# 1602.net
KiCad netlist of a schematic drawn in Altium Designer
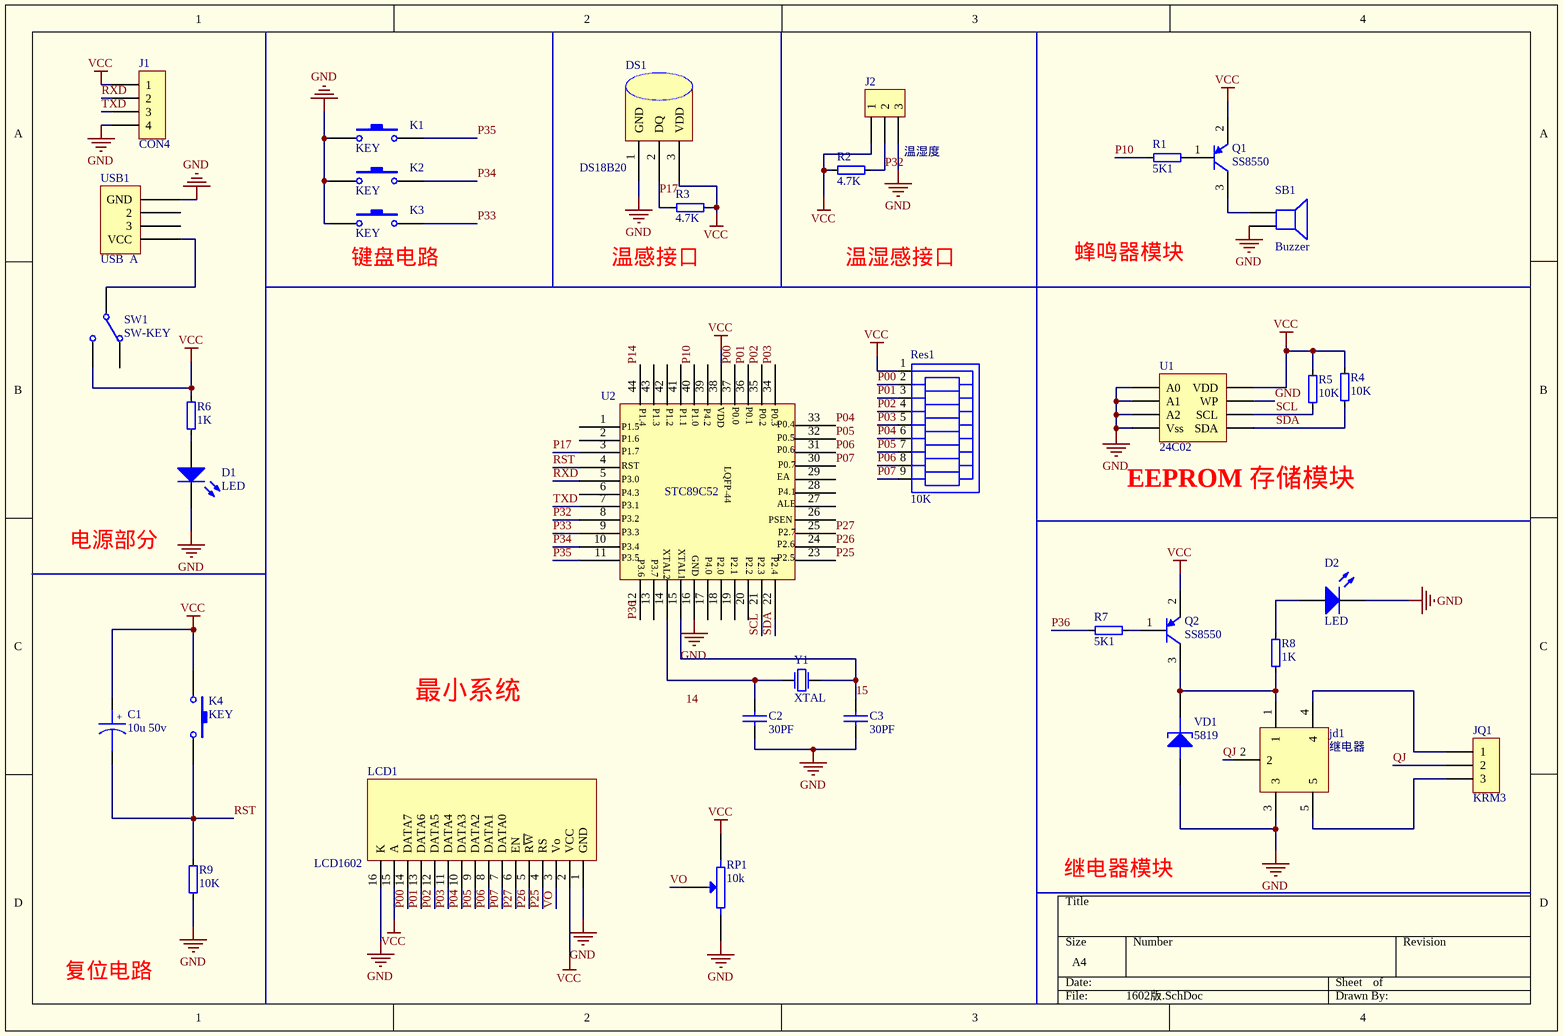
[diagram p0: 1602版.SchDoc]

(export (version "E")
  (design (tool "Eeschema 10.0.6"))
  (components
    (comp (ref "C1") (value "10u 50v") (footprint "10uf 50v") (libsource (lib "我的元件库2") (part "10u 50v")))
    (comp (ref "C2") (value "30PF") (footprint "C0805") (libsource (lib "阻容LED（集成）_Library") (part "CAP")))
    (comp (ref "C3") (value "30PF") (footprint "C0805") (libsource (lib "阻容LED（集成）_Library") (part "CAP")))
    (comp (ref "D1") (value "LED") (footprint "LED") (libsource (lib "我的元件库") (part "LED")))
    (comp (ref "D2") (value "LED") (footprint "LED") (libsource (lib "我的元件库") (part "LED")))
    (comp (ref "DS1") (value "DS18B20") (footprint "DS18B20") (libsource (lib "我的元件库") (part "DS18B20")))
    (comp (ref "J1") (value "CON4") (footprint "CON4") (libsource (lib "我的元件库2") (part "CON4")))
    (comp (ref "J2") (value "温湿度") (footprint "×3") (libsource (lib "我的元件库") (part "×3")))
    (comp (ref "jd1") (value "继电器") (footprint "继电器2") (libsource (lib "我的元件库2") (part "继电器2")))
    (comp (ref "JQ1") (value "KRM3") (footprint "KRM3") (libsource (lib "我的元件库2") (part "KRM3")))
    (comp (ref "K1") (value "KEY") (footprint "KEY") (libsource (lib "我的元件库") (part "KEY")))
    (comp (ref "K2") (value "KEY") (footprint "KEY") (libsource (lib "我的元件库") (part "KEY")))
    (comp (ref "K3") (value "KEY") (footprint "KEY") (libsource (lib "我的元件库") (part "KEY")))
    (comp (ref "K4") (value "KEY") (footprint "KEY") (libsource (lib "我的元件库") (part "KEY")))
    (comp (ref "LCD1") (value "LCD1602") (footprint "LCD1602") (libsource (lib "我的元件库2") (part "LCD1602")))
    (comp (ref "Q1")
      (value "SS8550")
      (footprint "SOT-23")
      (description "PNP贴片三极管")
      (fields (field (name "PUBLISHER") "Altium Limited"))
      (libsource (lib "Fszhang") (part "SS8550"))
    )
    (comp (ref "Q2")
      (value "SS8550")
      (footprint "SOT-23")
      (description "PNP贴片三极管")
      (fields (field (name "PUBLISHER") "Altium Limited"))
      (libsource (lib "Fszhang") (part "SS8550"))
    )
    (comp (ref "R1")
      (value "5K1")
      (footprint "R0805")
      (libsource (lib "阻容LED（集成）_Library") (part "RESistor"))
    )
    (comp (ref "R2")
      (value "4.7K")
      (footprint "R0805")
      (libsource (lib "阻容LED（集成）_Library") (part "RESistor"))
    )
    (comp (ref "R3")
      (value "4.7K")
      (footprint "R0805")
      (libsource (lib "阻容LED（集成）_Library") (part "RESistor"))
    )
    (comp (ref "R4")
      (value "10K")
      (footprint "R0805")
      (libsource (lib "阻容LED（集成）_Library") (part "RESistor"))
    )
    (comp (ref "R5")
      (value "10K")
      (footprint "R0805")
      (libsource (lib "阻容LED（集成）_Library") (part "RESistor"))
    )
    (comp (ref "R6") (value "1K") (footprint "R0805") (libsource (lib "阻容LED（集成）_Library") (part "RESistor")))
    (comp (ref "R7")
      (value "5K1")
      (footprint "R0805")
      (libsource (lib "阻容LED（集成）_Library") (part "RESistor"))
    )
    (comp (ref "R8") (value "1K") (footprint "R0805") (libsource (lib "阻容LED（集成）_Library") (part "RESistor")))
    (comp (ref "R9")
      (value "10K")
      (footprint "R0805")
      (libsource (lib "阻容LED（集成）_Library") (part "RESistor"))
    )
    (comp (ref "Res1") (value "10K") (footprint "Res-8") (libsource (lib "我的元件库2") (part "Res-8")))
    (comp (ref "RP1") (value "10k") (footprint "RE3296") (libsource (lib "我的元件库2") (part "RP1")))
    (comp (ref "SB1") (value "Buzzer") (footprint "BUZZER") (libsource (lib "我的元件库") (part "Buzzer")))
    (comp (ref "SW1") (value "SW-KEY") (footprint "SW-KEY") (libsource (lib "我的元件库") (part "SW-KEY")))
    (comp (ref "U1") (value "24C02") (footprint "24c02") (libsource (lib "我的元件库") (part "24C02")))
    (comp (ref "U2") (value "STC89C52") (footprint "TQFP-44") (libsource (lib "我的元件库") (part "STC89C----")))
    (comp (ref "USB1") (value "USB  A") (footprint "USB A") (libsource (lib "我的元件库2") (part "USB  A")))
    (comp (ref "VD1")
      (value "5819")
      (footprint "SS24二极管")
      (description "Tunnel FDiode")
      (libsource (lib "7971驱动板集成库Library1") (part "SS24二极管"))
    )
    (comp (ref "Y1") (value "XTAL") (footprint "XTAL") (libsource (lib "我的元件库2") (part "XTAL")))
  )
  (nets
    (net (code "2") (name "/15") (class "Default")
      (node (ref "C3") (pin "1") (pinfunction "1_1") (pintype "passive"))
      (node (ref "U2") (pin "15") (pinfunction "XTAL1_15") (pintype "passive"))
      (node (ref "Y1") (pin "2") (pinfunction "P2_2") (pintype "passive"))
    )
    (net (code "3") (name "/P00") (class "Default")
      (node (ref "LCD1") (pin "14") (pinfunction "DATA7_14") (pintype "passive"))
      (node (ref "Res1") (pin "2") (pintype "passive"))
      (node (ref "U2") (pin "37") (pinfunction "P0.0_37") (pintype "passive"))
    )
    (net (code "4") (name "/P01") (class "Default")
      (node (ref "LCD1") (pin "13") (pinfunction "DATA6_13") (pintype "passive"))
      (node (ref "Res1") (pin "3") (pintype "passive"))
      (node (ref "U2") (pin "36") (pinfunction "P0.1_36") (pintype "passive"))
    )
    (net (code "5") (name "/P02") (class "Default")
      (node (ref "LCD1") (pin "12") (pinfunction "DATA5_12") (pintype "passive"))
      (node (ref "Res1") (pin "4") (pintype "passive"))
      (node (ref "U2") (pin "35") (pinfunction "P0.2_35") (pintype "passive"))
    )
    (net (code "6") (name "/P03") (class "Default")
      (node (ref "LCD1") (pin "11") (pinfunction "DATA4_11") (pintype "passive"))
      (node (ref "Res1") (pin "5") (pintype "passive"))
      (node (ref "U2") (pin "34") (pinfunction "P0.3_34") (pintype "passive"))
    )
    (net (code "7") (name "/P04") (class "Default")
      (node (ref "LCD1") (pin "10") (pinfunction "DATA3_10") (pintype "passive"))
      (node (ref "Res1") (pin "6") (pintype "passive"))
      (node (ref "U2") (pin "33") (pinfunction "P0.4_33") (pintype "passive"))
    )
    (net (code "8") (name "/P05") (class "Default")
      (node (ref "LCD1") (pin "9") (pinfunction "DATA2_9") (pintype "passive"))
      (node (ref "Res1") (pin "7") (pintype "passive"))
      (node (ref "U2") (pin "32") (pinfunction "P0.5_32") (pintype "passive"))
    )
    (net (code "9") (name "/P06") (class "Default")
      (node (ref "LCD1") (pin "8") (pinfunction "DATA1_8") (pintype "passive"))
      (node (ref "Res1") (pin "8") (pintype "passive"))
      (node (ref "U2") (pin "31") (pinfunction "P0.6_31") (pintype "passive"))
    )
    (net (code "10") (name "/P07") (class "Default")
      (node (ref "LCD1") (pin "7") (pinfunction "DATA0_7") (pintype "passive"))
      (node (ref "Res1") (pin "9") (pintype "passive"))
      (node (ref "U2") (pin "30") (pinfunction "P0.7_30") (pintype "passive"))
    )
    (net (code "11") (name "/P10") (class "Default")
      (node (ref "R1") (pin "2") (pinfunction "2_2") (pintype "passive"))
      (node (ref "U2") (pin "40") (pinfunction "CLKOUT2/ADC0/P1.0_40") (pintype "passive"))
    )
    (net (code "12") (name "/P14") (class "Default")
      (node (ref "U2") (pin "44") (pinfunction "SS/CCP1/ADC4/P1.4_44") (pintype "passive"))
    )
    (net (code "13") (name "/P17") (class "Default")
      (node (ref "DS1") (pin "2") (pinfunction "DQ_2") (pintype "passive"))
      (node (ref "R3") (pin "2") (pinfunction "2_2") (pintype "passive"))
      (node (ref "U2") (pin "3") (pinfunction "MOSI/ADC67P1.7_3") (pintype "passive"))
    )
    (net (code "14") (name "/P25") (class "Default")
      (node (ref "LCD1") (pin "4") (pinfunction "RS_4") (pintype "passive"))
      (node (ref "U2") (pin "23") (pinfunction "P2.5/A13_23") (pintype "passive"))
    )
    (net (code "15") (name "/P26") (class "Default")
      (node (ref "LCD1") (pin "5") (pinfunction "R~{W}_5") (pintype "passive"))
      (node (ref "U2") (pin "24") (pinfunction "P2.6/A14_24") (pintype "passive"))
    )
    (net (code "16") (name "/P27") (class "Default")
      (node (ref "LCD1") (pin "6") (pinfunction "EN_6") (pintype "passive"))
      (node (ref "U2") (pin "25") (pinfunction "P2.7/A15_25") (pintype "passive"))
    )
    (net (code "17") (name "/P32") (class "Default")
      (node (ref "J2") (pin "2") (pinfunction "2_2") (pintype "passive"))
      (node (ref "R2") (pin "1") (pinfunction "1_1") (pintype "passive"))
      (node (ref "U2") (pin "8") (pinfunction "~{INTO}/P3.2_8") (pintype "passive"))
    )
    (net (code "18") (name "/P33") (class "Default")
      (node (ref "K3") (pin "2") (pinfunction "2_2") (pintype "passive"))
      (node (ref "U2") (pin "9") (pinfunction "~{INT1}/P3.3_9") (pintype "passive"))
    )
    (net (code "19") (name "/P34") (class "Default")
      (node (ref "K2") (pin "2") (pinfunction "2_2") (pintype "passive"))
      (node (ref "U2") (pin "10") (pinfunction "CLKOUT0/~{INT}/T0/P3.4_10") (pintype "passive"))
    )
    (net (code "20") (name "/P35") (class "Default")
      (node (ref "K1") (pin "2") (pinfunction "2_2") (pintype "passive"))
      (node (ref "U2") (pin "11") (pinfunction "CLKOUT1/~{INT}/T1/P3.5_11") (pintype "passive"))
    )
    (net (code "21") (name "/P36") (class "Default")
      (node (ref "R7") (pin "2") (pinfunction "2_2") (pintype "passive"))
      (node (ref "U2") (pin "12") (pinfunction "P3.6/~{WR}_12") (pintype "passive"))
    )
    (net (code "22") (name "/QJ") (class "Default")
      (node (ref "JQ1") (pin "2") (pinfunction "2_2") (pintype "passive"))
      (node (ref "jd1") (pin "2") (pinfunction "2_2") (pintype "passive"))
    )
    (net (code "23") (name "/RST") (class "Default")
      (node (ref "C1") (pin "2") (pinfunction "2_2") (pintype "passive"))
      (node (ref "K4") (pin "2") (pinfunction "2_2") (pintype "passive"))
      (node (ref "R9") (pin "2") (pinfunction "2_2") (pintype "passive"))
      (node (ref "U2") (pin "4") (pinfunction "RST_4") (pintype "passive"))
    )
    (net (code "24") (name "/RXD") (class "Default")
      (node (ref "J1") (pin "2") (pinfunction "2_2") (pintype "passive"))
      (node (ref "U2") (pin "5") (pinfunction "~{INT}/RXD/P3.0_5") (pintype "passive"))
    )
    (net (code "25") (name "/SCL") (class "Default")
      (node (ref "R5") (pin "1") (pinfunction "1_1") (pintype "passive"))
      (node (ref "U1") (pin "6") (pinfunction "SCL_6") (pintype "passive"))
      (node (ref "U2") (pin "21") (pinfunction "P2.3/A11_21") (pintype "passive"))
    )
    (net (code "26") (name "/SDA") (class "Default")
      (node (ref "R4") (pin "1") (pinfunction "1_1") (pintype "passive"))
      (node (ref "U1") (pin "5") (pinfunction "SDA_5") (pintype "passive"))
      (node (ref "U2") (pin "22") (pinfunction "P2.4/A12_22") (pintype "passive"))
    )
    (net (code "27") (name "/TXD") (class "Default")
      (node (ref "J1") (pin "3") (pinfunction "3_3") (pintype "passive"))
      (node (ref "U2") (pin "7") (pinfunction "TXD/P3.1_7") (pintype "passive"))
    )
    (net (code "28") (name "/VO") (class "Default")
      (node (ref "LCD1") (pin "3") (pinfunction "Vo_3") (pintype "passive"))
      (node (ref "RP1") (pin "3") (pinfunction "3_3") (pintype "passive"))
    )
    (net (code "29") (name "GND") (class "Default")
      (node (ref "C2") (pin "2") (pinfunction "2_2") (pintype "passive"))
      (node (ref "C3") (pin "2") (pinfunction "2_2") (pintype "passive"))
      (node (ref "D1") (pin "2") (pinfunction "2_2") (pintype "passive"))
      (node (ref "D2") (pin "2") (pinfunction "2_2") (pintype "passive"))
      (node (ref "DS1") (pin "1") (pinfunction "GND_1") (pintype "passive"))
      (node (ref "J1") (pin "4") (pinfunction "4_4") (pintype "passive"))
      (node (ref "J2") (pin "3") (pinfunction "3_3") (pintype "passive"))
      (node (ref "K1") (pin "1") (pinfunction "1_1") (pintype "passive"))
      (node (ref "K2") (pin "1") (pinfunction "1_1") (pintype "passive"))
      (node (ref "K3") (pin "1") (pinfunction "1_1") (pintype "passive"))
      (node (ref "LCD1") (pin "1") (pinfunction "GND_1") (pintype "passive"))
      (node (ref "LCD1") (pin "16") (pinfunction "K_16") (pintype "passive"))
      (node (ref "R9") (pin "1") (pinfunction "1_1") (pintype "passive"))
      (node (ref "RP1") (pin "1") (pinfunction "1_1") (pintype "passive"))
      (node (ref "SB1") (pin "2") (pinfunction "2_2") (pintype "passive"))
      (node (ref "U1") (pin "1") (pinfunction "A0_1") (pintype "passive"))
      (node (ref "U1") (pin "2") (pinfunction "A1_2") (pintype "passive"))
      (node (ref "U1") (pin "3") (pinfunction "A2_3") (pintype "passive"))
      (node (ref "U1") (pin "4") (pinfunction "Vss_4") (pintype "passive"))
      (node (ref "U1") (pin "7") (pinfunction "WP_7") (pintype "passive"))
      (node (ref "U2") (pin "16") (pinfunction "VSS_16") (pintype "passive"))
      (node (ref "USB1") (pin "1") (pinfunction "GND_1") (pintype "passive"))
      (node (ref "VD1") (pin "1") (pinfunction "A_1") (pintype "passive"))
      (node (ref "jd1") (pin "3") (pinfunction "3_3") (pintype "passive"))
    )
    (net (code "30") (name "Net-(D1-Pad1)") (class "Default")
      (node (ref "D1") (pin "1") (pinfunction "1_1") (pintype "passive"))
      (node (ref "R6") (pin "2") (pinfunction "2_2") (pintype "passive"))
    )
    (net (code "31") (name "Net-(D2-Pad1)") (class "Default")
      (node (ref "D2") (pin "1") (pinfunction "1_1") (pintype "passive"))
      (node (ref "R8") (pin "1") (pinfunction "1_1") (pintype "passive"))
    )
    (net (code "32") (name "Net-(JQ1-Pad1)") (class "Default")
      (node (ref "JQ1") (pin "1") (pinfunction "1_1") (pintype "passive"))
      (node (ref "jd1") (pin "4") (pinfunction "4_4") (pintype "passive"))
    )
    (net (code "33") (name "Net-(JQ1-Pad3)") (class "Default")
      (node (ref "JQ1") (pin "3") (pinfunction "3_3") (pintype "passive"))
      (node (ref "jd1") (pin "5") (pinfunction "5_5") (pintype "passive"))
    )
    (net (code "34") (name "Net-(Q1-B)") (class "Default")
      (node (ref "Q1") (pin "1") (pinfunction "B_1") (pintype "passive"))
      (node (ref "R1") (pin "1") (pinfunction "1_1") (pintype "passive"))
    )
    (net (code "35") (name "Net-(Q1-C)") (class "Default")
      (node (ref "Q1") (pin "3") (pinfunction "C_3") (pintype "passive"))
      (node (ref "SB1") (pin "1") (pinfunction "1_1") (pintype "passive"))
    )
    (net (code "36") (name "Net-(Q2-B)") (class "Default")
      (node (ref "Q2") (pin "1") (pinfunction "B_1") (pintype "passive"))
      (node (ref "R7") (pin "1") (pinfunction "1_1") (pintype "passive"))
    )
    (net (code "37") (name "Net-(Q2-C)") (class "Default")
      (node (ref "Q2") (pin "3") (pinfunction "C_3") (pintype "passive"))
      (node (ref "R8") (pin "2") (pinfunction "2_2") (pintype "passive"))
      (node (ref "VD1") (pin "2") (pinfunction "K_2") (pintype "passive"))
      (node (ref "jd1") (pin "1") (pinfunction "1_1") (pintype "passive"))
    )
    (net (code "38") (name "Net-(SW1-COMMON1)") (class "Default")
      (node (ref "SW1") (pin "1") (pinfunction "COMMON1_1") (pintype "passive"))
      (node (ref "USB1") (pin "4") (pinfunction "VCC_4") (pintype "passive"))
    )
    (net (code "39") (name "Net-(U2-XTAL2)") (class "Default")
      (node (ref "C2") (pin "1") (pinfunction "1_1") (pintype "passive"))
      (node (ref "U2") (pin "14") (pinfunction "XTAL2_14") (pintype "passive"))
      (node (ref "Y1") (pin "1") (pinfunction "P1_1") (pintype "passive"))
    )
    (net (code "40") (name "VCC") (class "Default")
      (node (ref "C1") (pin "1") (pinfunction "1_1") (pintype "passive"))
      (node (ref "DS1") (pin "3") (pinfunction "VDD_3") (pintype "passive"))
      (node (ref "J1") (pin "1") (pinfunction "1_1") (pintype "passive"))
      (node (ref "J2") (pin "1") (pinfunction "1_1") (pintype "passive"))
      (node (ref "K4") (pin "1") (pinfunction "1_1") (pintype "passive"))
      (node (ref "LCD1") (pin "15") (pinfunction "A_15") (pintype "passive"))
      (node (ref "LCD1") (pin "2") (pinfunction "VCC_2") (pintype "passive"))
      (node (ref "Q1") (pin "2") (pinfunction "E_2") (pintype "passive"))
      (node (ref "Q2") (pin "2") (pinfunction "E_2") (pintype "passive"))
      (node (ref "R2") (pin "2") (pinfunction "2_2") (pintype "passive"))
      (node (ref "R3") (pin "1") (pinfunction "1_1") (pintype "passive"))
      (node (ref "R4") (pin "2") (pinfunction "2_2") (pintype "passive"))
      (node (ref "R5") (pin "2") (pinfunction "2_2") (pintype "passive"))
      (node (ref "R6") (pin "1") (pinfunction "1_1") (pintype "passive"))
      (node (ref "RP1") (pin "2") (pinfunction "2_2") (pintype "passive"))
      (node (ref "Res1") (pin "1") (pintype "passive"))
      (node (ref "SW1") (pin "2") (pinfunction "NO1_2") (pintype "passive"))
      (node (ref "U1") (pin "8") (pinfunction "VDD_8") (pintype "passive"))
      (node (ref "U2") (pin "38") (pinfunction "VDD_38") (pintype "passive"))
    )
    (net (code "41") (name "unconnected-(SW1-NC1-Pad3)") (class "Default")
      (node (ref "SW1") (pin "3") (pinfunction "NC1_3") (pintype "passive"))
    )
    (net (code "42") (name "unconnected-(U2-ADC1{slash}P1.1-Pad41)") (class "Default")
      (node (ref "U2") (pin "41") (pinfunction "ADC1/P1.1_41") (pintype "passive"))
    )
    (net (code "43") (name "unconnected-(U2-ALE{slash}P4.5-Pad27)") (class "Default")
      (node (ref "U2") (pin "27") (pinfunction "ALE/P4.5_27") (pintype "passive"))
    )
    (net (code "44") (name "unconnected-(U2-EX_LVD{slash}P4.6{slash}RST2-Pad29)") (class "Default")
      (node (ref "U2") (pin "29") (pinfunction "EX_LVD/P4.6/RST2_29") (pintype "passive"))
    )
    (net (code "45") (name "unconnected-(U2-MISO{slash}RXD2{slash}CCP0{slash}P4.2-Pad39)") (class "Default")
      (node (ref "U2") (pin "39") (pinfunction "MISO/RXD2/CCP0/P4.2_39") (pintype "passive"))
    )
    (net (code "46") (name "unconnected-(U2-MOSI{slash}ADC5{slash}P1.5-Pad1)") (class "Default")
      (node (ref "U2") (pin "1") (pinfunction "MOSI/ADC5/P1.5_1") (pintype "passive"))
    )
    (net (code "47") (name "unconnected-(U2-MOSI{slash}ADC6{slash}P1.6-Pad2)") (class "Default")
      (node (ref "U2") (pin "2") (pinfunction "MOSI/ADC6/P1.6_2") (pintype "passive"))
    )
    (net (code "48") (name "unconnected-(U2-NA{slash}P4.4-Pad26)") (class "Default")
      (node (ref "U2") (pin "26") (pinfunction "NA/P4.4_26") (pintype "passive"))
    )
    (net (code "49") (name "unconnected-(U2-P2.0{slash}A18-Pad18)") (class "Default")
      (node (ref "U2") (pin "18") (pinfunction "P2.0/A18_18") (pintype "passive"))
    )
    (net (code "50") (name "unconnected-(U2-P2.1{slash}A9-Pad19)") (class "Default")
      (node (ref "U2") (pin "19") (pinfunction "P2.1/A9_19") (pintype "passive"))
    )
    (net (code "51") (name "unconnected-(U2-P2.2{slash}A10-Pad20)") (class "Default")
      (node (ref "U2") (pin "20") (pinfunction "P2.2/A10_20") (pintype "passive"))
    )
    (net (code "52") (name "unconnected-(U2-P3.7{slash}~{RD}-Pad13)") (class "Default")
      (node (ref "U2") (pin "13") (pinfunction "P3.7/~{RD}_13") (pintype "passive"))
    )
    (net (code "53") (name "unconnected-(U2-P4.0{slash}SS-Pad17)") (class "Default")
      (node (ref "U2") (pin "17") (pinfunction "P4.0/SS_17") (pintype "passive"))
    )
    (net (code "54") (name "unconnected-(U2-P4.1{slash}ECI{slash}MOSI-Pad28)") (class "Default")
      (node (ref "U2") (pin "28") (pinfunction "P4.1/ECI/MOSI_28") (pintype "passive"))
    )
    (net (code "55") (name "unconnected-(U2-RXD2{slash}ECI{slash}ADC2{slash}P1.2-Pad42)") (class "Default")
      (node (ref "U2") (pin "42") (pinfunction "RXD2/ECI/ADC2/P1.2_42") (pintype "passive"))
    )
    (net (code "56") (name "unconnected-(U2-SCLK{slash}TXD2{slash}CCP1{slash}P4.3-Pad6)") (class "Default")
      (node (ref "U2") (pin "6") (pinfunction "SCLK/TXD2/CCP1/P4.3_6") (pintype "passive"))
    )
    (net (code "57") (name "unconnected-(U2-TXD2{slash}CCP0{slash}ADC3{slash}P1.3-Pad43)") (class "Default")
      (node (ref "U2") (pin "43") (pinfunction "TXD2/CCP0/ADC3/P1.3_43") (pintype "passive"))
    )
    (net (code "58") (name "unconnected-(USB1-Pad2)") (class "Default")
      (node (ref "USB1") (pin "2") (pinfunction "2_2") (pintype "passive"))
    )
    (net (code "59") (name "unconnected-(USB1-Pad3)") (class "Default")
      (node (ref "USB1") (pin "3") (pinfunction "3_3") (pintype "passive"))
    )
  )
)
